# FAN_Unit_250316.net
KiCad netlist of a schematic drawn in Altium Designer
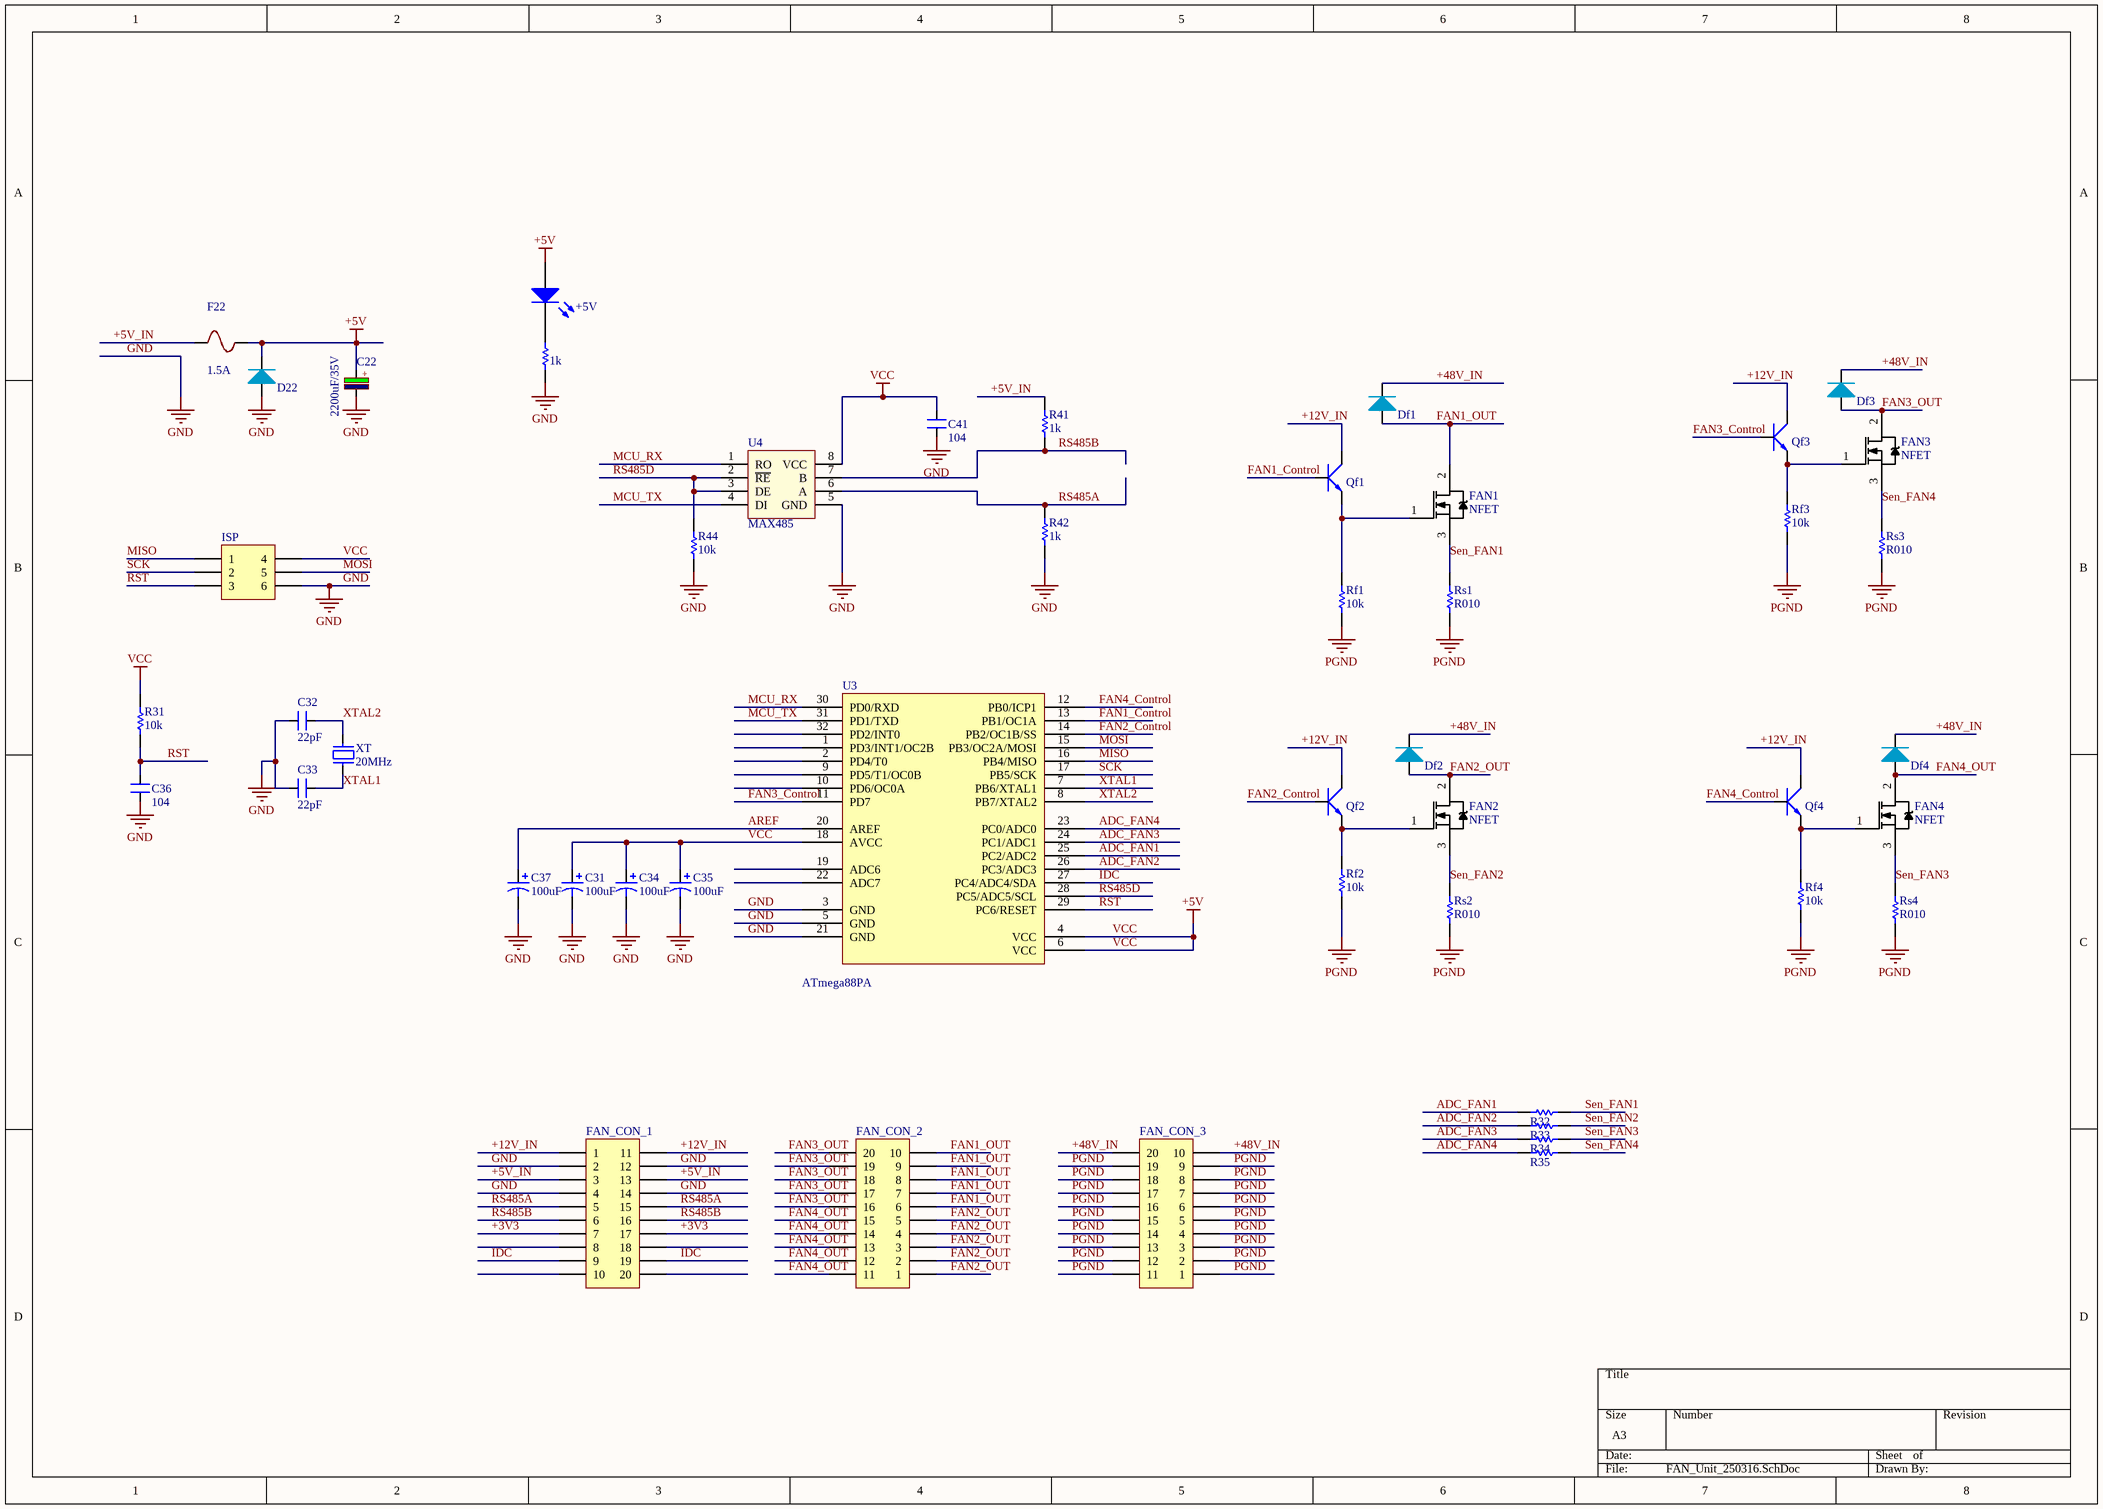
[diagram p0: FAN_Unit_250316.SchDoc]

(export (version "E")
  (design (tool "Eeschema 10.0.6"))
  (components
    (comp (ref "+5V") (value "Led") (footprint "LED 5mm RED") (libsource (lib "Tuan") (part "Led")))
    (comp (ref "C22")
      (value "2200uF/35V")
      (footprint "PBL - SMD Packages:CAP_ELEC_SIZE_G")
      (description "Cap 1000uF/16V - 220uF/50V")
      (libsource (lib "heromap") (part "CP4"))
    )
    (comp (ref "C31")
      (value "100uF")
      (footprint "CAPC2012N_F")
      (fields (field (name "Comment") "Cap"))
      (libsource (lib "Tuan") (part "Cap"))
    )
    (comp (ref "C32")
      (value "22pF")
      (footprint "CAPC1608N")
      (fields (field (name "Comment") "CAP NP"))
      (libsource (lib "Tuan") (part "CAP NP"))
    )
    (comp (ref "C33")
      (value "22pF")
      (footprint "CAPC1608N")
      (fields (field (name "Comment") "CAP NP"))
      (libsource (lib "Tuan") (part "CAP NP"))
    )
    (comp (ref "C34")
      (value "100uF")
      (footprint "CAPC2012N_F")
      (fields (field (name "Comment") "Cap"))
      (libsource (lib "Tuan") (part "Cap"))
    )
    (comp (ref "C35")
      (value "100uF")
      (footprint "CAPC2012N_F")
      (fields (field (name "Comment") "Cap"))
      (libsource (lib "Tuan") (part "Cap"))
    )
    (comp (ref "C36")
      (value "104")
      (footprint "CAPC1608N")
      (fields (field (name "Comment") "CAP NP"))
      (libsource (lib "Tuan") (part "CAP NP"))
    )
    (comp (ref "C37")
      (value "100uF")
      (footprint "CAPC2012N_F")
      (fields (field (name "Comment") "Cap"))
      (libsource (lib "Tuan") (part "Cap"))
    )
    (comp (ref "C41")
      (value "104")
      (footprint "CAPC2012N_F")
      (fields (field (name "Comment") "100nF/104"))
      (libsource (lib "Tuan") (part "CAP NP"))
    )
    (comp (ref "D22") (value "Diode") (footprint "DO-214AC") (libsource (lib "Tuan") (part "Diode")))
    (comp (ref "Df1") (value "Diode") (footprint "DO-214AC") (libsource (lib "Tuan") (part "Diode")))
    (comp (ref "Df2") (value "Diode") (footprint "DO-214AC") (libsource (lib "Tuan") (part "Diode")))
    (comp (ref "Df3") (value "Diode") (footprint "DO-214AC") (libsource (lib "Tuan") (part "Diode")))
    (comp (ref "Df4") (value "Diode") (footprint "DO-214AC") (libsource (lib "Tuan") (part "Diode")))
    (comp (ref "F22") (value "1.5A") (footprint "FUSE_SR-5-BK") (libsource (lib "Tuan") (part "Fuse")))
    (comp (ref "FAN1") (value "NFET") (footprint "TO-252") (libsource (lib "Tuan") (part "NFET")))
    (comp (ref "FAN2") (value "NFET") (footprint "TO-252") (libsource (lib "Tuan") (part "NFET")))
    (comp (ref "FAN3") (value "NFET") (footprint "TO-252") (libsource (lib "Tuan") (part "NFET")))
    (comp (ref "FAN4") (value "NFET") (footprint "TO-252") (libsource (lib "Tuan") (part "NFET")))
    (comp (ref "FAN_CON_1")
      (value "Header 10X2A")
      (footprint "OMC10")
      (description "Header, 10-Pin, Dual row")
      (fields (field (name "PUBLISHER") "Altium Limited"))
      (libsource (lib "") (part "Header 10X2A_1"))
    )
    (comp (ref "FAN_CON_2")
      (value "Header 10X2A")
      (footprint "OMC10")
      (description "Header, 10-Pin, Dual row")
      (fields (field (name "PUBLISHER") "Altium Limited"))
      (libsource (lib "Miscellaneous Connectors") (part "Header 10X2A"))
    )
    (comp (ref "FAN_CON_3")
      (value "Header 10X2A")
      (footprint "OMC10")
      (description "Header, 10-Pin, Dual row")
      (fields (field (name "PUBLISHER") "Altium Limited"))
      (libsource (lib "Miscellaneous Connectors") (part "Header 10X2A"))
    )
    (comp (ref "ISP")
      (value "Header 3X2A")
      (footprint "HDR2X3_CEN")
      (description "Header, 3-Pin, Dual row")
      (fields (field (name "PUBLISHER") "Altium Limited"))
      (libsource (lib "Miscellaneous Connectors") (part "Header 3X2A"))
    )
    (comp (ref "Qf1")
      (value "C828")
      (footprint "SOT23 TOP")
      (description "Transistor C828 C1815....")
      (libsource (lib "Tuan") (part "NPN"))
    )
    (comp (ref "Qf2")
      (value "C828")
      (footprint "SOT23 TOP")
      (description "Transistor C828 C1815....")
      (libsource (lib "Tuan") (part "NPN"))
    )
    (comp (ref "Qf3")
      (value "C828")
      (footprint "SOT23 TOP")
      (description "Transistor C828 C1815....")
      (libsource (lib "Tuan") (part "NPN"))
    )
    (comp (ref "Qf4")
      (value "C828")
      (footprint "SOT23 TOP")
      (description "Transistor C828 C1815....")
      (libsource (lib "Tuan") (part "NPN"))
    )
    (comp (ref "R22")
      (value "1k")
      (footprint "RESC2012N_F")
      (fields (field (name "Comment") "Res_0805_1k"))
      (libsource (lib "Tuan") (part "Res"))
    )
    (comp (ref "R31")
      (value "10k")
      (footprint "RESC1608N_ZERO")
      (fields (field (name "Comment") "Res"))
      (libsource (lib "Tuan") (part "Res"))
    )
    (comp (ref "R32") (value "Res") (footprint "RESC1608N_ZERO") (libsource (lib "Tuan") (part "Res")))
    (comp (ref "R33") (value "Res") (footprint "RESC1608N_ZERO") (libsource (lib "Tuan") (part "Res")))
    (comp (ref "R34") (value "Res") (footprint "RESC1608N_ZERO") (libsource (lib "Tuan") (part "Res")))
    (comp (ref "R35") (value "Res") (footprint "RESC1608N_ZERO") (libsource (lib "Tuan") (part "Res")))
    (comp (ref "R41")
      (value "1k")
      (footprint "RESC1608N_ZERO")
      (description "Tro dan")
      (libsource (lib "GPS_Clock_v12") (part "Res"))
    )
    (comp (ref "R42")
      (value "1k")
      (footprint "RESC1608N_ZERO")
      (description "Tro dan")
      (libsource (lib "GPS_Clock_v12") (part "Res"))
    )
    (comp (ref "R44")
      (value "10k")
      (footprint "RESC1608N_ZERO")
      (description "Tro dan")
      (fields (field (name "Comment") "330R"))
      (libsource (lib "GPS_Clock_v12") (part "Res"))
    )
    (comp (ref "Rf1")
      (value "10k")
      (footprint "RESC2012N_F")
      (fields (field (name "Comment") "Res"))
      (libsource (lib "Tuan") (part "Res"))
    )
    (comp (ref "Rf2")
      (value "10k")
      (footprint "RESC2012N_F")
      (fields (field (name "Comment") "Res"))
      (libsource (lib "Tuan") (part "Res"))
    )
    (comp (ref "Rf3")
      (value "10k")
      (footprint "RESC2012N_F")
      (fields (field (name "Comment") "Res"))
      (libsource (lib "Tuan") (part "Res"))
    )
    (comp (ref "Rf4")
      (value "10k")
      (footprint "RESC2012N_F")
      (fields (field (name "Comment") "Res"))
      (libsource (lib "Tuan") (part "Res"))
    )
    (comp (ref "Rs1")
      (value "R010")
      (footprint "RESC6332N")
      (fields (field (name "Comment") "Res"))
      (libsource (lib "Tuan") (part "Res"))
    )
    (comp (ref "Rs2")
      (value "R010")
      (footprint "RESC6332N")
      (fields (field (name "Comment") "Res"))
      (libsource (lib "Tuan") (part "Res"))
    )
    (comp (ref "Rs3")
      (value "R010")
      (footprint "RESC6332N")
      (fields (field (name "Comment") "Res"))
      (libsource (lib "Tuan") (part "Res"))
    )
    (comp (ref "Rs4")
      (value "R010")
      (footprint "RESC6332N")
      (fields (field (name "Comment") "Res"))
      (libsource (lib "Tuan") (part "Res"))
    )
    (comp (ref "U3")
      (value "ATmega88PA")
      (footprint "32PIN")
      (description "ATmega48/168/328")
      (libsource (lib "Tuan") (part "ATmega48/168/328"))
    )
    (comp (ref "U4")
      (value "MAX485")
      (footprint "SO-8")
      (description "RS232 - RS485 (Same sn75176)")
      (libsource (lib "heromap") (part "MAX485"))
    )
    (comp (ref "XT") (value "20MHz") (footprint "XT2") (libsource (lib "Tuan") (part "Crystal")))
  )
  (nets
    (net (code "1") (name "+5V") (class "Default")
      (node (ref "+5V") (pin "1") (pinfunction "A_1") (pintype "passive"))
      (node (ref "C22") (pin "1") (pinfunction "1_1") (pintype "passive"))
      (node (ref "C31") (pin "1") (pinfunction "1_1") (pintype "passive"))
      (node (ref "C34") (pin "1") (pinfunction "1_1") (pintype "passive"))
      (node (ref "C35") (pin "1") (pinfunction "1_1") (pintype "passive"))
      (node (ref "C41") (pin "2") (pinfunction "2_2") (pintype "passive"))
      (node (ref "D22") (pin "2") (pinfunction "K_2") (pintype "passive"))
      (node (ref "F22") (pin "2") (pinfunction "2_2") (pintype "passive"))
      (node (ref "ISP") (pin "4") (pinfunction "4_4") (pintype "passive"))
      (node (ref "R31") (pin "2") (pinfunction "2_2") (pintype "passive"))
      (node (ref "U3") (pin "18") (pinfunction "AVCC_18") (pintype "passive"))
      (node (ref "U3") (pin "4") (pinfunction "VCC_4") (pintype "passive"))
      (node (ref "U3") (pin "6") (pinfunction "VCC_6") (pintype "passive"))
      (node (ref "U4") (pin "8") (pinfunction "VCC_8") (pintype "passive"))
    )
    (net (code "2") (name "/+3V3") (class "Default")
      (node (ref "FAN_CON_1") (pin "17") (pinfunction "17_17") (pintype "passive"))
      (node (ref "FAN_CON_1") (pin "7") (pinfunction "7_7") (pintype "passive"))
    )
    (net (code "3") (name "/+5V_IN") (class "Default")
      (node (ref "F22") (pin "1") (pinfunction "1_1") (pintype "passive"))
      (node (ref "FAN_CON_1") (pin "13") (pinfunction "13_13") (pintype "passive"))
      (node (ref "FAN_CON_1") (pin "3") (pinfunction "3_3") (pintype "passive"))
      (node (ref "R41") (pin "2") (pinfunction "2_2") (pintype "passive"))
    )
    (net (code "4") (name "/+12V_IN") (class "Default")
      (node (ref "FAN_CON_1") (pin "1") (pinfunction "1_1") (pintype "passive"))
      (node (ref "FAN_CON_1") (pin "11") (pinfunction "11_11") (pintype "passive"))
      (node (ref "Qf1") (pin "2") (pinfunction "C_2") (pintype "passive"))
      (node (ref "Qf2") (pin "2") (pinfunction "C_2") (pintype "passive"))
      (node (ref "Qf3") (pin "2") (pinfunction "C_2") (pintype "passive"))
      (node (ref "Qf4") (pin "2") (pinfunction "C_2") (pintype "passive"))
    )
    (net (code "5") (name "/+48V_IN") (class "Default")
      (node (ref "Df1") (pin "2") (pinfunction "K_2") (pintype "passive"))
      (node (ref "Df2") (pin "2") (pinfunction "K_2") (pintype "passive"))
      (node (ref "Df3") (pin "2") (pinfunction "K_2") (pintype "passive"))
      (node (ref "Df4") (pin "2") (pinfunction "K_2") (pintype "passive"))
      (node (ref "FAN_CON_3") (pin "10") (pinfunction "10_10") (pintype "passive"))
      (node (ref "FAN_CON_3") (pin "20") (pinfunction "20_20") (pintype "passive"))
    )
    (net (code "6") (name "/ADC_FAN1") (class "Default")
      (node (ref "R32") (pin "1") (pinfunction "1_1") (pintype "passive"))
      (node (ref "U3") (pin "25") (pinfunction "PC2/ADC2_25") (pintype "passive"))
    )
    (net (code "7") (name "/ADC_FAN2") (class "Default")
      (node (ref "R33") (pin "1") (pinfunction "1_1") (pintype "passive"))
      (node (ref "U3") (pin "26") (pinfunction "PC3/ADC3_26") (pintype "passive"))
    )
    (net (code "8") (name "/ADC_FAN3") (class "Default")
      (node (ref "R34") (pin "1") (pinfunction "1_1") (pintype "passive"))
      (node (ref "U3") (pin "24") (pinfunction "PC1/ADC1_24") (pintype "passive"))
    )
    (net (code "9") (name "/ADC_FAN4") (class "Default")
      (node (ref "R35") (pin "1") (pinfunction "1_1") (pintype "passive"))
      (node (ref "U3") (pin "23") (pinfunction "PC0/ADC0_23") (pintype "passive"))
    )
    (net (code "10") (name "/AREF") (class "Default")
      (node (ref "C37") (pin "1") (pinfunction "1_1") (pintype "passive"))
      (node (ref "U3") (pin "20") (pinfunction "AREF_20") (pintype "passive"))
    )
    (net (code "11") (name "/FAN1_Control") (class "Default")
      (node (ref "Qf1") (pin "1") (pinfunction "B_1") (pintype "passive"))
      (node (ref "U3") (pin "13") (pinfunction "PB1/OC1A_13") (pintype "passive"))
    )
    (net (code "12") (name "/FAN1_OUT") (class "Default")
      (node (ref "Df1") (pin "1") (pinfunction "A_1") (pintype "passive"))
      (node (ref "FAN1") (pin "2") (pinfunction "D_2") (pintype "passive"))
      (node (ref "FAN_CON_2") (pin "10") (pinfunction "10_10") (pintype "passive"))
      (node (ref "FAN_CON_2") (pin "6") (pinfunction "6_6") (pintype "passive"))
      (node (ref "FAN_CON_2") (pin "7") (pinfunction "7_7") (pintype "passive"))
      (node (ref "FAN_CON_2") (pin "8") (pinfunction "8_8") (pintype "passive"))
      (node (ref "FAN_CON_2") (pin "9") (pinfunction "9_9") (pintype "passive"))
    )
    (net (code "13") (name "/FAN2_Control") (class "Default")
      (node (ref "Qf2") (pin "1") (pinfunction "B_1") (pintype "passive"))
      (node (ref "U3") (pin "14") (pinfunction "PB2/OC1B/SS_14") (pintype "passive"))
    )
    (net (code "14") (name "/FAN2_OUT") (class "Default")
      (node (ref "Df2") (pin "1") (pinfunction "A_1") (pintype "passive"))
      (node (ref "FAN2") (pin "2") (pinfunction "D_2") (pintype "passive"))
      (node (ref "FAN_CON_2") (pin "1") (pinfunction "1_1") (pintype "passive"))
      (node (ref "FAN_CON_2") (pin "2") (pinfunction "2_2") (pintype "passive"))
      (node (ref "FAN_CON_2") (pin "3") (pinfunction "3_3") (pintype "passive"))
      (node (ref "FAN_CON_2") (pin "4") (pinfunction "4_4") (pintype "passive"))
      (node (ref "FAN_CON_2") (pin "5") (pinfunction "5_5") (pintype "passive"))
    )
    (net (code "15") (name "/FAN3_Control") (class "Default")
      (node (ref "Qf3") (pin "1") (pinfunction "B_1") (pintype "passive"))
      (node (ref "U3") (pin "11") (pinfunction "PD7_11") (pintype "passive"))
    )
    (net (code "16") (name "/FAN3_OUT") (class "Default")
      (node (ref "Df3") (pin "1") (pinfunction "A_1") (pintype "passive"))
      (node (ref "FAN3") (pin "2") (pinfunction "D_2") (pintype "passive"))
      (node (ref "FAN_CON_2") (pin "16") (pinfunction "16_16") (pintype "passive"))
      (node (ref "FAN_CON_2") (pin "17") (pinfunction "17_17") (pintype "passive"))
      (node (ref "FAN_CON_2") (pin "18") (pinfunction "18_18") (pintype "passive"))
      (node (ref "FAN_CON_2") (pin "19") (pinfunction "19_19") (pintype "passive"))
      (node (ref "FAN_CON_2") (pin "20") (pinfunction "20_20") (pintype "passive"))
    )
    (net (code "17") (name "/FAN4_Control") (class "Default")
      (node (ref "Qf4") (pin "1") (pinfunction "B_1") (pintype "passive"))
      (node (ref "U3") (pin "12") (pinfunction "PB0/ICP1_12") (pintype "passive"))
    )
    (net (code "18") (name "/FAN4_OUT") (class "Default")
      (node (ref "Df4") (pin "1") (pinfunction "A_1") (pintype "passive"))
      (node (ref "FAN4") (pin "2") (pinfunction "D_2") (pintype "passive"))
      (node (ref "FAN_CON_2") (pin "11") (pinfunction "11_11") (pintype "passive"))
      (node (ref "FAN_CON_2") (pin "12") (pinfunction "12_12") (pintype "passive"))
      (node (ref "FAN_CON_2") (pin "13") (pinfunction "13_13") (pintype "passive"))
      (node (ref "FAN_CON_2") (pin "14") (pinfunction "14_14") (pintype "passive"))
      (node (ref "FAN_CON_2") (pin "15") (pinfunction "15_15") (pintype "passive"))
    )
    (net (code "19") (name "/IDC") (class "Default")
      (node (ref "FAN_CON_1") (pin "19") (pinfunction "19_19") (pintype "passive"))
      (node (ref "FAN_CON_1") (pin "9") (pinfunction "9_9") (pintype "passive"))
      (node (ref "U3") (pin "27") (pinfunction "PC4/ADC4/SDA_27") (pintype "passive"))
    )
    (net (code "20") (name "/MCU_RX") (class "Default")
      (node (ref "U3") (pin "30") (pinfunction "PD0/RXD_30") (pintype "passive"))
      (node (ref "U4") (pin "1") (pinfunction "RO_1") (pintype "passive"))
    )
    (net (code "21") (name "/MCU_TX") (class "Default")
      (node (ref "U3") (pin "31") (pinfunction "PD1/TXD_31") (pintype "passive"))
      (node (ref "U4") (pin "4") (pinfunction "DI_4") (pintype "passive"))
    )
    (net (code "22") (name "/MISO") (class "Default")
      (node (ref "ISP") (pin "1") (pinfunction "1_1") (pintype "passive"))
      (node (ref "U3") (pin "16") (pinfunction "PB4/MISO_16") (pintype "passive"))
    )
    (net (code "23") (name "/MOSI") (class "Default")
      (node (ref "ISP") (pin "5") (pinfunction "5_5") (pintype "passive"))
      (node (ref "U3") (pin "15") (pinfunction "PB3/OC2A/MOSI_15") (pintype "passive"))
    )
    (net (code "24") (name "/RS485A") (class "Default")
      (node (ref "FAN_CON_1") (pin "15") (pinfunction "15_15") (pintype "passive"))
      (node (ref "FAN_CON_1") (pin "5") (pinfunction "5_5") (pintype "passive"))
      (node (ref "R42") (pin "2") (pinfunction "2_2") (pintype "passive"))
      (node (ref "U4") (pin "6") (pinfunction "A_6") (pintype "passive"))
    )
    (net (code "25") (name "/RS485B") (class "Default")
      (node (ref "FAN_CON_1") (pin "16") (pinfunction "16_16") (pintype "passive"))
      (node (ref "FAN_CON_1") (pin "6") (pinfunction "6_6") (pintype "passive"))
      (node (ref "R41") (pin "1") (pinfunction "1_1") (pintype "passive"))
      (node (ref "U4") (pin "7") (pinfunction "B_7") (pintype "passive"))
    )
    (net (code "26") (name "/RS485D") (class "Default")
      (node (ref "R44") (pin "2") (pinfunction "2_2") (pintype "passive"))
      (node (ref "U3") (pin "28") (pinfunction "PC5/ADC5/SCL_28") (pintype "passive"))
      (node (ref "U4") (pin "2") (pinfunction "~{RE}_2") (pintype "passive"))
      (node (ref "U4") (pin "3") (pinfunction "DE_3") (pintype "passive"))
    )
    (net (code "27") (name "/RST") (class "Default")
      (node (ref "C36") (pin "2") (pinfunction "2_2") (pintype "passive"))
      (node (ref "ISP") (pin "3") (pinfunction "3_3") (pintype "passive"))
      (node (ref "R31") (pin "1") (pinfunction "1_1") (pintype "passive"))
      (node (ref "U3") (pin "29") (pinfunction "PC6/RESET_29") (pintype "passive"))
    )
    (net (code "28") (name "/SCK") (class "Default")
      (node (ref "ISP") (pin "2") (pinfunction "2_2") (pintype "passive"))
      (node (ref "U3") (pin "17") (pinfunction "PB5/SCK_17") (pintype "passive"))
    )
    (net (code "29") (name "/Sen_FAN1") (class "Default")
      (node (ref "FAN1") (pin "3") (pinfunction "S_3") (pintype "passive"))
      (node (ref "R32") (pin "2") (pinfunction "2_2") (pintype "passive"))
      (node (ref "Rs1") (pin "2") (pinfunction "2_2") (pintype "passive"))
    )
    (net (code "30") (name "/Sen_FAN2") (class "Default")
      (node (ref "FAN2") (pin "3") (pinfunction "S_3") (pintype "passive"))
      (node (ref "R33") (pin "2") (pinfunction "2_2") (pintype "passive"))
      (node (ref "Rs2") (pin "2") (pinfunction "2_2") (pintype "passive"))
    )
    (net (code "31") (name "/Sen_FAN3") (class "Default")
      (node (ref "FAN4") (pin "3") (pinfunction "S_3") (pintype "passive"))
      (node (ref "R34") (pin "2") (pinfunction "2_2") (pintype "passive"))
      (node (ref "Rs4") (pin "2") (pinfunction "2_2") (pintype "passive"))
    )
    (net (code "32") (name "/Sen_FAN4") (class "Default")
      (node (ref "FAN3") (pin "3") (pinfunction "S_3") (pintype "passive"))
      (node (ref "R35") (pin "2") (pinfunction "2_2") (pintype "passive"))
      (node (ref "Rs3") (pin "2") (pinfunction "2_2") (pintype "passive"))
    )
    (net (code "33") (name "/XTAL1") (class "Default")
      (node (ref "C33") (pin "1") (pinfunction "1_1") (pintype "passive"))
      (node (ref "U3") (pin "7") (pinfunction "PB6/XTAL1_7") (pintype "passive"))
      (node (ref "XT") (pin "1") (pinfunction "1_1") (pintype "passive"))
    )
    (net (code "34") (name "/XTAL2") (class "Default")
      (node (ref "C32") (pin "1") (pinfunction "1_1") (pintype "passive"))
      (node (ref "U3") (pin "8") (pinfunction "PB7/XTAL2_8") (pintype "passive"))
      (node (ref "XT") (pin "2") (pinfunction "2_2") (pintype "passive"))
    )
    (net (code "35") (name "GND") (class "Default")
      (node (ref "C22") (pin "2") (pinfunction "2_2") (pintype "passive"))
      (node (ref "C31") (pin "2") (pinfunction "2_2") (pintype "passive"))
      (node (ref "C32") (pin "2") (pinfunction "2_2") (pintype "passive"))
      (node (ref "C33") (pin "2") (pinfunction "2_2") (pintype "passive"))
      (node (ref "C34") (pin "2") (pinfunction "2_2") (pintype "passive"))
      (node (ref "C35") (pin "2") (pinfunction "2_2") (pintype "passive"))
      (node (ref "C36") (pin "1") (pinfunction "1_1") (pintype "passive"))
      (node (ref "C37") (pin "2") (pinfunction "2_2") (pintype "passive"))
      (node (ref "C41") (pin "1") (pinfunction "1_1") (pintype "passive"))
      (node (ref "D22") (pin "1") (pinfunction "A_1") (pintype "passive"))
      (node (ref "FAN_CON_1") (pin "12") (pinfunction "12_12") (pintype "passive"))
      (node (ref "FAN_CON_1") (pin "14") (pinfunction "14_14") (pintype "passive"))
      (node (ref "FAN_CON_1") (pin "2") (pinfunction "2_2") (pintype "passive"))
      (node (ref "FAN_CON_1") (pin "4") (pinfunction "4_4") (pintype "passive"))
      (node (ref "ISP") (pin "6") (pinfunction "6_6") (pintype "passive"))
      (node (ref "R22") (pin "2") (pinfunction "2_2") (pintype "passive"))
      (node (ref "R42") (pin "1") (pinfunction "1_1") (pintype "passive"))
      (node (ref "R44") (pin "1") (pinfunction "1_1") (pintype "passive"))
      (node (ref "U3") (pin "21") (pinfunction "GND_21") (pintype "power_in"))
      (node (ref "U3") (pin "3") (pinfunction "GND_3") (pintype "power_in"))
      (node (ref "U3") (pin "5") (pinfunction "GND_5") (pintype "power_in"))
      (node (ref "U4") (pin "5") (pinfunction "GND_5") (pintype "passive"))
    )
    (net (code "36") (name "Net-(+5V-K)") (class "Default")
      (node (ref "+5V") (pin "2") (pinfunction "K_2") (pintype "passive"))
      (node (ref "R22") (pin "1") (pinfunction "1_1") (pintype "passive"))
    )
    (net (code "37") (name "Net-(FAN1-G)") (class "Default")
      (node (ref "FAN1") (pin "1") (pinfunction "G_1") (pintype "passive"))
      (node (ref "Qf1") (pin "3") (pinfunction "E_3") (pintype "passive"))
      (node (ref "Rf1") (pin "2") (pinfunction "2_2") (pintype "passive"))
    )
    (net (code "38") (name "Net-(FAN2-G)") (class "Default")
      (node (ref "FAN2") (pin "1") (pinfunction "G_1") (pintype "passive"))
      (node (ref "Qf2") (pin "3") (pinfunction "E_3") (pintype "passive"))
      (node (ref "Rf2") (pin "2") (pinfunction "2_2") (pintype "passive"))
    )
    (net (code "39") (name "Net-(FAN3-G)") (class "Default")
      (node (ref "FAN3") (pin "1") (pinfunction "G_1") (pintype "passive"))
      (node (ref "Qf3") (pin "3") (pinfunction "E_3") (pintype "passive"))
      (node (ref "Rf3") (pin "2") (pinfunction "2_2") (pintype "passive"))
    )
    (net (code "40") (name "Net-(FAN4-G)") (class "Default")
      (node (ref "FAN4") (pin "1") (pinfunction "G_1") (pintype "passive"))
      (node (ref "Qf4") (pin "3") (pinfunction "E_3") (pintype "passive"))
      (node (ref "Rf4") (pin "2") (pinfunction "2_2") (pintype "passive"))
    )
    (net (code "41") (name "PGND") (class "Default")
      (node (ref "FAN_CON_3") (pin "1") (pinfunction "1_1") (pintype "passive"))
      (node (ref "FAN_CON_3") (pin "11") (pinfunction "11_11") (pintype "passive"))
      (node (ref "FAN_CON_3") (pin "12") (pinfunction "12_12") (pintype "passive"))
      (node (ref "FAN_CON_3") (pin "13") (pinfunction "13_13") (pintype "passive"))
      (node (ref "FAN_CON_3") (pin "14") (pinfunction "14_14") (pintype "passive"))
      (node (ref "FAN_CON_3") (pin "15") (pinfunction "15_15") (pintype "passive"))
      (node (ref "FAN_CON_3") (pin "16") (pinfunction "16_16") (pintype "passive"))
      (node (ref "FAN_CON_3") (pin "17") (pinfunction "17_17") (pintype "passive"))
      (node (ref "FAN_CON_3") (pin "18") (pinfunction "18_18") (pintype "passive"))
      (node (ref "FAN_CON_3") (pin "19") (pinfunction "19_19") (pintype "passive"))
      (node (ref "FAN_CON_3") (pin "2") (pinfunction "2_2") (pintype "passive"))
      (node (ref "FAN_CON_3") (pin "3") (pinfunction "3_3") (pintype "passive"))
      (node (ref "FAN_CON_3") (pin "4") (pinfunction "4_4") (pintype "passive"))
      (node (ref "FAN_CON_3") (pin "5") (pinfunction "5_5") (pintype "passive"))
      (node (ref "FAN_CON_3") (pin "6") (pinfunction "6_6") (pintype "passive"))
      (node (ref "FAN_CON_3") (pin "7") (pinfunction "7_7") (pintype "passive"))
      (node (ref "FAN_CON_3") (pin "8") (pinfunction "8_8") (pintype "passive"))
      (node (ref "FAN_CON_3") (pin "9") (pinfunction "9_9") (pintype "passive"))
      (node (ref "Rf1") (pin "1") (pinfunction "1_1") (pintype "passive"))
      (node (ref "Rf2") (pin "1") (pinfunction "1_1") (pintype "passive"))
      (node (ref "Rf3") (pin "1") (pinfunction "1_1") (pintype "passive"))
      (node (ref "Rf4") (pin "1") (pinfunction "1_1") (pintype "passive"))
      (node (ref "Rs1") (pin "1") (pinfunction "1_1") (pintype "passive"))
      (node (ref "Rs2") (pin "1") (pinfunction "1_1") (pintype "passive"))
      (node (ref "Rs3") (pin "1") (pinfunction "1_1") (pintype "passive"))
      (node (ref "Rs4") (pin "1") (pinfunction "1_1") (pintype "passive"))
    )
    (net (code "42") (name "unconnected-(FAN_CON_1-Pad8)") (class "Default")
      (node (ref "FAN_CON_1") (pin "8") (pinfunction "8_8") (pintype "passive"))
    )
    (net (code "43") (name "unconnected-(FAN_CON_1-Pad10)") (class "Default")
      (node (ref "FAN_CON_1") (pin "10") (pinfunction "10_10") (pintype "passive"))
    )
    (net (code "44") (name "unconnected-(FAN_CON_1-Pad18)") (class "Default")
      (node (ref "FAN_CON_1") (pin "18") (pinfunction "18_18") (pintype "passive"))
    )
    (net (code "45") (name "unconnected-(FAN_CON_1-Pad20)") (class "Default")
      (node (ref "FAN_CON_1") (pin "20") (pinfunction "20_20") (pintype "passive"))
    )
    (net (code "46") (name "unconnected-(U3-ADC6-Pad19)") (class "Default")
      (node (ref "U3") (pin "19") (pinfunction "ADC6_19") (pintype "passive"))
    )
    (net (code "47") (name "unconnected-(U3-ADC7-Pad22)") (class "Default")
      (node (ref "U3") (pin "22") (pinfunction "ADC7_22") (pintype "passive"))
    )
    (net (code "48") (name "unconnected-(U3-PD2{slash}INT0-Pad32)") (class "Default")
      (node (ref "U3") (pin "32") (pinfunction "PD2/INT0_32") (pintype "passive"))
    )
    (net (code "49") (name "unconnected-(U3-PD3{slash}INT1{slash}OC2B-Pad1)") (class "Default")
      (node (ref "U3") (pin "1") (pinfunction "PD3/INT1/OC2B_1") (pintype "passive"))
    )
    (net (code "50") (name "unconnected-(U3-PD4{slash}T0-Pad2)") (class "Default")
      (node (ref "U3") (pin "2") (pinfunction "PD4/T0_2") (pintype "passive"))
    )
    (net (code "51") (name "unconnected-(U3-PD5{slash}T1{slash}OC0B-Pad9)") (class "Default")
      (node (ref "U3") (pin "9") (pinfunction "PD5/T1/OC0B_9") (pintype "passive"))
    )
    (net (code "52") (name "unconnected-(U3-PD6{slash}OC0A-Pad10)") (class "Default")
      (node (ref "U3") (pin "10") (pinfunction "PD6/OC0A_10") (pintype "passive"))
    )
  )
)
